# Temperature_cube_NEO_V2.net
KiCad netlist of a schematic drawn in EAGLE
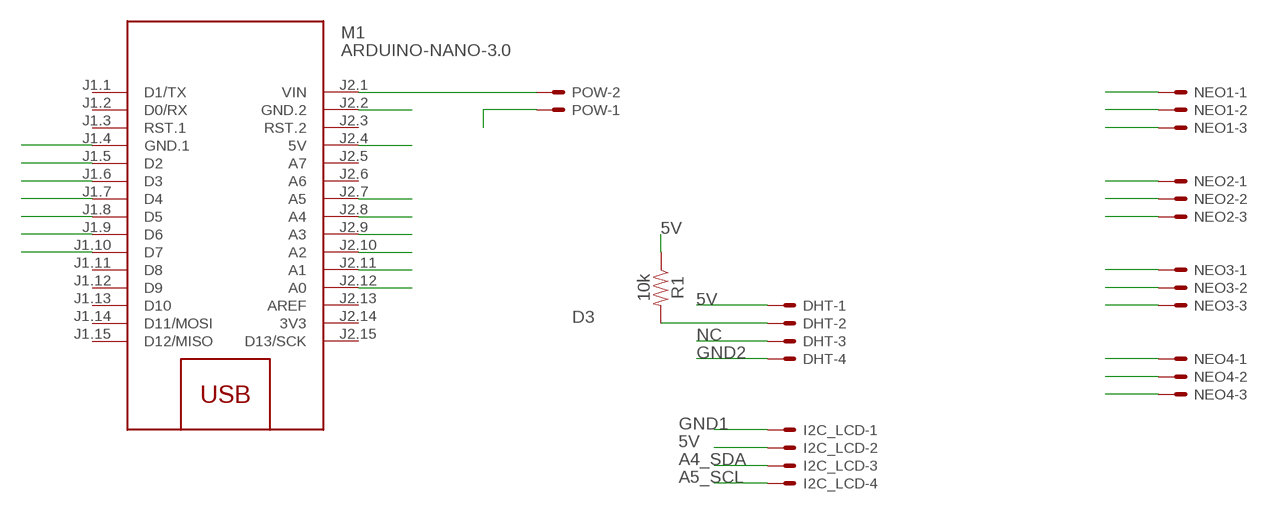
[diagram p0: schematic, sheet 1]

(export (version "E")
  (design (tool "Eeschema 10.0.6"))
  (components
    (comp (ref "DHT")
      (value "JST-XH-04-PIN-ROUND-PAD")
      (footprint "eagle-import:JST-XH-04-PACKAGE-ROUND-PAD")
      (libsource (lib "eagle-import") (part "JST-XH-04-PIN-ROUND-PAD"))
    )
    (comp (ref "I2C_LCD")
      (value "JST-XH-04-PIN-ROUND-PAD")
      (footprint "eagle-import:JST-XH-04-PACKAGE-ROUND-PAD")
      (libsource (lib "eagle-import") (part "JST-XH-04-PIN-ROUND-PAD"))
    )
    (comp (ref "M1")
      (value "ARDUINO-NANO-3.0")
      (footprint "eagle-import:ARDUINO-NANO-3.0")
      (libsource (lib "eagle-import") (part "ARDUINO-NANO-3.0"))
    )
    (comp (ref "NEO1")
      (value "JST-XH-03-PIN-ROUND-PAD")
      (footprint "eagle-import:JST-XH-03-PACKAGE-ROUND-PAD")
      (libsource (lib "eagle-import") (part "JST-XH-03-PIN-ROUND-PAD"))
    )
    (comp (ref "NEO2")
      (value "JST-XH-03-PIN-ROUND-PAD")
      (footprint "eagle-import:JST-XH-03-PACKAGE-ROUND-PAD")
      (libsource (lib "eagle-import") (part "JST-XH-03-PIN-ROUND-PAD"))
    )
    (comp (ref "NEO3")
      (value "JST-XH-03-PIN-ROUND-PAD")
      (footprint "eagle-import:JST-XH-03-PACKAGE-ROUND-PAD")
      (libsource (lib "eagle-import") (part "JST-XH-03-PIN-ROUND-PAD"))
    )
    (comp (ref "NEO4")
      (value "JST-XH-03-PIN-ROUND-PAD")
      (footprint "eagle-import:JST-XH-03-PACKAGE-ROUND-PAD")
      (libsource (lib "eagle-import") (part "JST-XH-03-PIN-ROUND-PAD"))
    )
    (comp (ref "POW")
      (value "JST-XH-02-PIN-ROUND-PAD")
      (footprint "eagle-import:JST-XH-02-PACKAGE-ROUND-PAD")
      (libsource (lib "eagle-import") (part "JST-XH-02-PIN-ROUND-PAD"))
    )
    (comp (ref "R1")
      (value "10k")
      (footprint "eagle-import:AXIAL-0.3")
      (libsource (lib "eagle-import") (part "1KOHM-HORIZ-1/4W-1%"))
    )
  )
  (nets
    (net (code "1") (name "3V3") (class "Default")
      (node (ref "M1") (pin "J2.14") (pinfunction "3V3_J2.14") (pintype "power_in"))
    )
    (net (code "2") (name "5V") (class "Default")
      (node (ref "DHT") (pin "1") (pinfunction "S_1") (pintype "passive"))
      (node (ref "I2C_LCD") (pin "2") (pinfunction "S_2") (pintype "passive"))
      (node (ref "M1") (pin "J2.4") (pinfunction "5V_J2.4") (pintype "power_in"))
      (node (ref "NEO1") (pin "1") (pinfunction "S_1") (pintype "passive"))
      (node (ref "NEO2") (pin "1") (pinfunction "S_1") (pintype "passive"))
      (node (ref "NEO3") (pin "1") (pinfunction "S_1") (pintype "passive"))
      (node (ref "NEO4") (pin "1") (pinfunction "S_1") (pintype "passive"))
      (node (ref "R1") (pin "P$1") (pinfunction "1_P$1") (pintype "passive"))
    )
    (net (code "3") (name "A0") (class "Default")
      (node (ref "M1") (pin "J2.12") (pinfunction "A0_J2.12") (pintype "bidirectional"))
      (node (ref "NEO1") (pin "2") (pinfunction "S_2") (pintype "passive"))
    )
    (net (code "4") (name "A1") (class "Default")
      (node (ref "M1") (pin "J2.11") (pinfunction "A1_J2.11") (pintype "bidirectional"))
      (node (ref "NEO2") (pin "2") (pinfunction "S_2") (pintype "passive"))
    )
    (net (code "5") (name "A2") (class "Default")
      (node (ref "M1") (pin "J2.10") (pinfunction "A2_J2.10") (pintype "bidirectional"))
      (node (ref "NEO3") (pin "2") (pinfunction "S_2") (pintype "passive"))
    )
    (net (code "6") (name "A3") (class "Default")
      (node (ref "M1") (pin "J2.9") (pinfunction "A3_J2.9") (pintype "bidirectional"))
      (node (ref "NEO4") (pin "2") (pinfunction "S_2") (pintype "passive"))
    )
    (net (code "7") (name "A4_SDA") (class "Default")
      (node (ref "I2C_LCD") (pin "3") (pinfunction "S_3") (pintype "passive"))
      (node (ref "M1") (pin "J2.8") (pinfunction "A4_J2.8") (pintype "bidirectional"))
    )
    (net (code "8") (name "A5_SCL") (class "Default")
      (node (ref "I2C_LCD") (pin "4") (pinfunction "S_4") (pintype "passive"))
      (node (ref "M1") (pin "J2.7") (pinfunction "A5_J2.7") (pintype "bidirectional"))
    )
    (net (code "9") (name "D3") (class "Default")
      (node (ref "DHT") (pin "2") (pinfunction "S_2") (pintype "passive"))
      (node (ref "M1") (pin "J1.6") (pinfunction "D3_J1.6") (pintype "bidirectional"))
      (node (ref "R1") (pin "P$2") (pinfunction "2_P$2") (pintype "passive"))
    )
    (net (code "10") (name "GND1") (class "Default")
      (node (ref "I2C_LCD") (pin "1") (pinfunction "S_1") (pintype "passive"))
      (node (ref "M1") (pin "J1.4") (pinfunction "GND.1_J1.4") (pintype "power_in"))
      (node (ref "NEO3") (pin "3") (pinfunction "S_3") (pintype "passive"))
      (node (ref "NEO4") (pin "3") (pinfunction "S_3") (pintype "passive"))
    )
    (net (code "11") (name "GND2") (class "Default")
      (node (ref "DHT") (pin "4") (pinfunction "S_4") (pintype "passive"))
      (node (ref "M1") (pin "J2.2") (pinfunction "GND.2_J2.2") (pintype "power_in"))
      (node (ref "NEO1") (pin "3") (pinfunction "S_3") (pintype "passive"))
      (node (ref "NEO2") (pin "3") (pinfunction "S_3") (pintype "passive"))
      (node (ref "POW") (pin "1") (pinfunction "S_1") (pintype "passive"))
    )
    (net (code "12") (name "NC") (class "Default")
      (node (ref "DHT") (pin "3") (pinfunction "S_3") (pintype "passive"))
    )
    (net (code "13") (name "Net-(M1-VIN)") (class "Default")
      (node (ref "M1") (pin "J2.1") (pinfunction "VIN_J2.1") (pintype "power_in"))
      (node (ref "POW") (pin "2") (pinfunction "S_2") (pintype "passive"))
    )
    (net (code "14") (name "unconnected-(M1-A6-PadJ2.6)") (class "Default")
      (node (ref "M1") (pin "J2.6") (pinfunction "A6_J2.6") (pintype "bidirectional"))
    )
    (net (code "15") (name "unconnected-(M1-A7-PadJ2.5)") (class "Default")
      (node (ref "M1") (pin "J2.5") (pinfunction "A7_J2.5") (pintype "bidirectional"))
    )
    (net (code "16") (name "unconnected-(M1-AREF-PadJ2.13)") (class "Default")
      (node (ref "M1") (pin "J2.13") (pinfunction "AREF_J2.13") (pintype "bidirectional"))
    )
    (net (code "17") (name "unconnected-(M1-D0{slash}RX-PadJ1.2)") (class "Default")
      (node (ref "M1") (pin "J1.2") (pinfunction "D0/RX_J1.2") (pintype "bidirectional"))
    )
    (net (code "18") (name "unconnected-(M1-D1{slash}TX-PadJ1.1)") (class "Default")
      (node (ref "M1") (pin "J1.1") (pinfunction "D1/TX_J1.1") (pintype "bidirectional"))
    )
    (net (code "19") (name "unconnected-(M1-D2-PadJ1.5)") (class "Default")
      (node (ref "M1") (pin "J1.5") (pinfunction "D2_J1.5") (pintype "bidirectional"))
    )
    (net (code "20") (name "unconnected-(M1-D4-PadJ1.7)") (class "Default")
      (node (ref "M1") (pin "J1.7") (pinfunction "D4_J1.7") (pintype "bidirectional"))
    )
    (net (code "21") (name "unconnected-(M1-D5-PadJ1.8)") (class "Default")
      (node (ref "M1") (pin "J1.8") (pinfunction "D5_J1.8") (pintype "bidirectional"))
    )
    (net (code "22") (name "unconnected-(M1-D6-PadJ1.9)") (class "Default")
      (node (ref "M1") (pin "J1.9") (pinfunction "D6_J1.9") (pintype "bidirectional"))
    )
    (net (code "23") (name "unconnected-(M1-D7-PadJ1.10)") (class "Default")
      (node (ref "M1") (pin "J1.10") (pinfunction "D7_J1.10") (pintype "bidirectional"))
    )
    (net (code "24") (name "unconnected-(M1-D8-PadJ1.11)") (class "Default")
      (node (ref "M1") (pin "J1.11") (pinfunction "D8_J1.11") (pintype "bidirectional"))
    )
    (net (code "25") (name "unconnected-(M1-D9-PadJ1.12)") (class "Default")
      (node (ref "M1") (pin "J1.12") (pinfunction "D9_J1.12") (pintype "bidirectional"))
    )
    (net (code "26") (name "unconnected-(M1-D10-PadJ1.13)") (class "Default")
      (node (ref "M1") (pin "J1.13") (pinfunction "D10_J1.13") (pintype "bidirectional"))
    )
    (net (code "27") (name "unconnected-(M1-D11{slash}MOSI-PadJ1.14)") (class "Default")
      (node (ref "M1") (pin "J1.14") (pinfunction "D11/MOSI_J1.14") (pintype "bidirectional"))
    )
    (net (code "28") (name "unconnected-(M1-D12{slash}MISO-PadJ1.15)") (class "Default")
      (node (ref "M1") (pin "J1.15") (pinfunction "D12/MISO_J1.15") (pintype "bidirectional"))
    )
    (net (code "29") (name "unconnected-(M1-D13{slash}SCK-PadJ2.15)") (class "Default")
      (node (ref "M1") (pin "J2.15") (pinfunction "D13/SCK_J2.15") (pintype "bidirectional"))
    )
    (net (code "30") (name "unconnected-(M1-RST.1-PadJ1.3)") (class "Default")
      (node (ref "M1") (pin "J1.3") (pinfunction "RST.1_J1.3") (pintype "bidirectional"))
    )
    (net (code "31") (name "unconnected-(M1-RST.2-PadJ2.3)") (class "Default")
      (node (ref "M1") (pin "J2.3") (pinfunction "RST.2_J2.3") (pintype "bidirectional"))
    )
  )
)
